# AEMLIC_V2_1.net
KiCad netlist of a schematic drawn in EAGLE
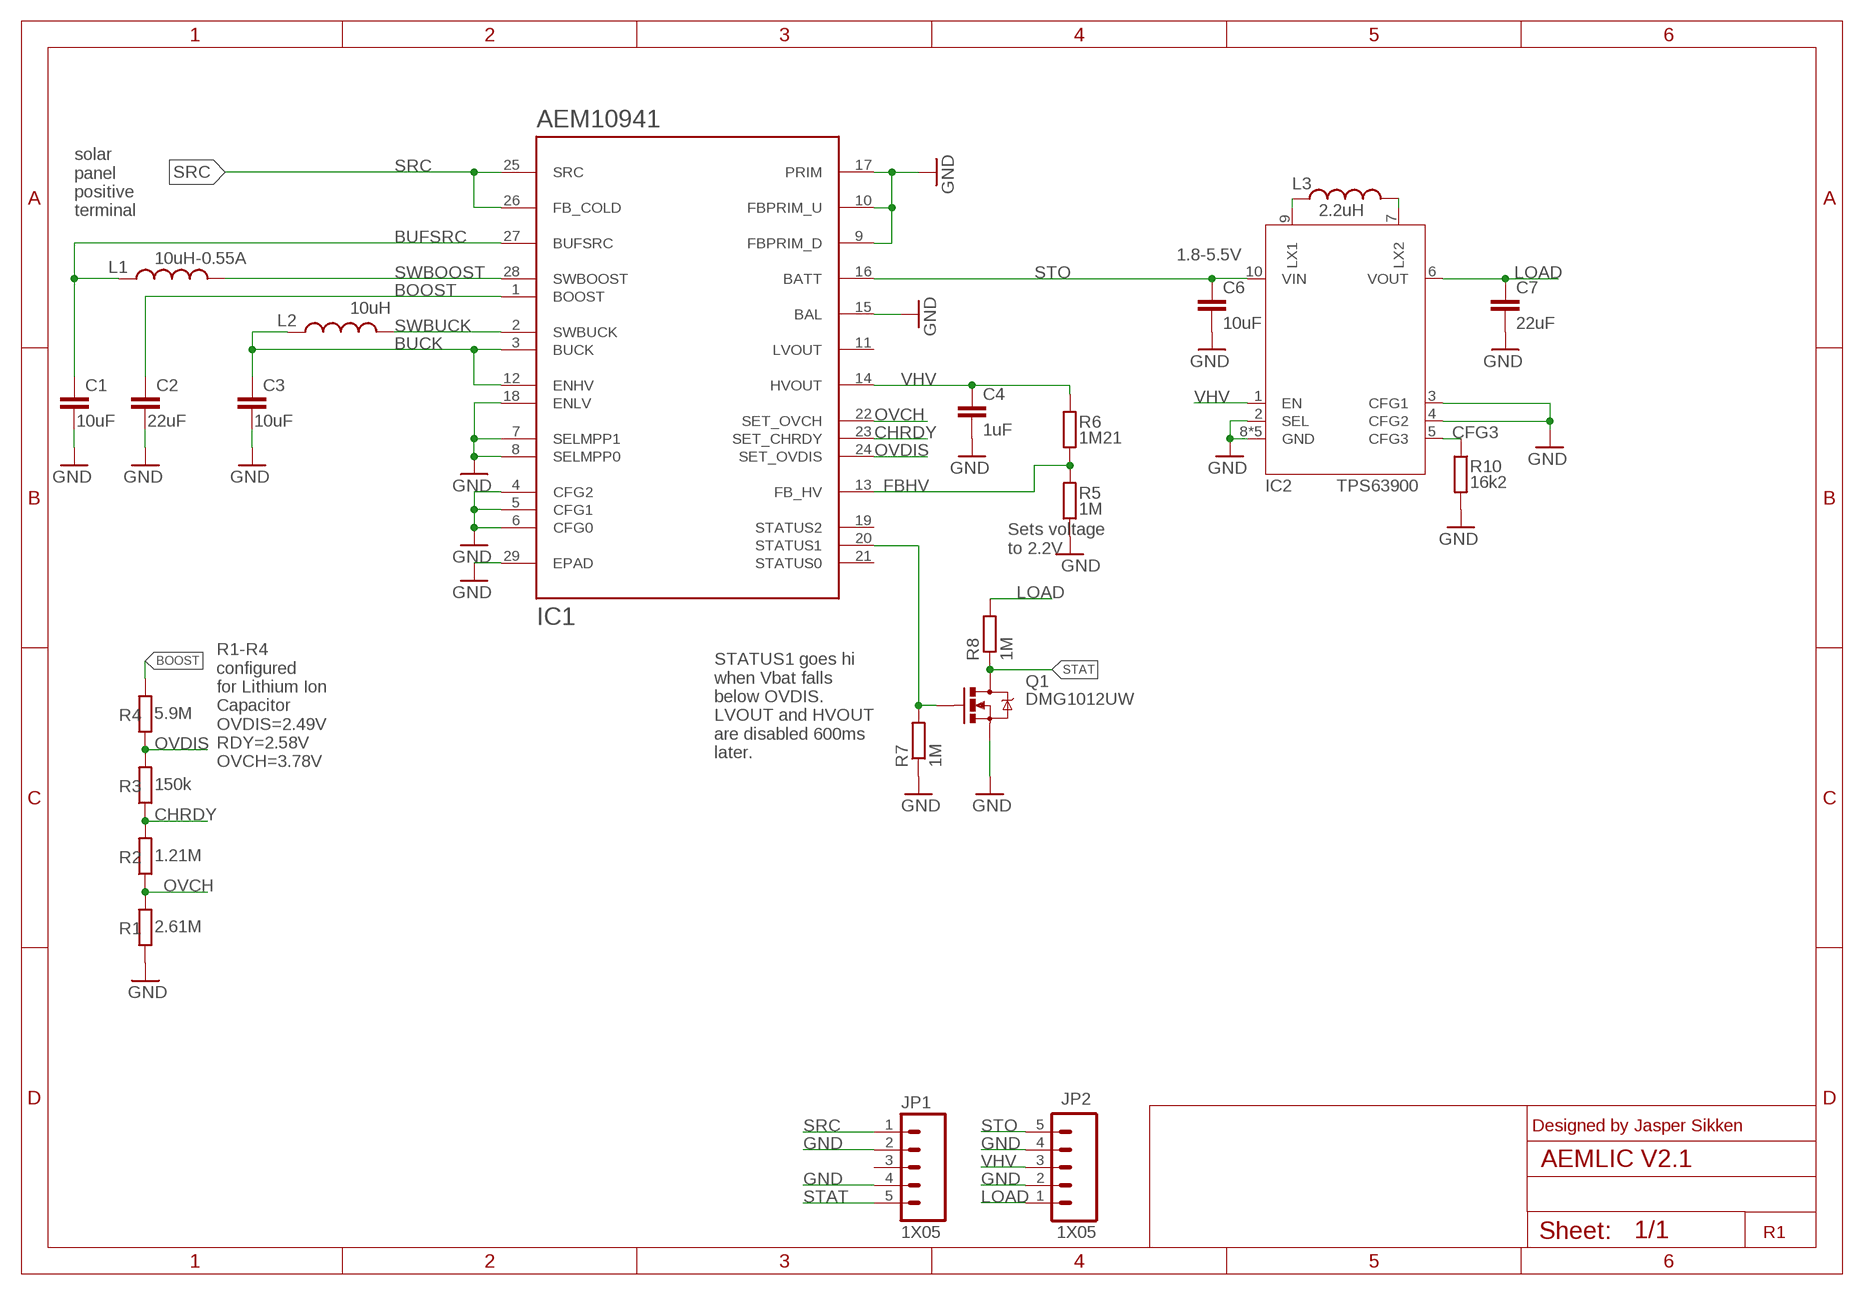
[diagram p0: schematic, sheet 1]

(export (version "E")
  (design (tool "Eeschema 10.0.6"))
  (components
    (comp (ref "C1")
      (value "10uF")
      (footprint "eagle-import:C0603")
      (fields
        (field (name "MF") "Taiyo Yuden")
        (field (name "MPN") "LMK107BBJ106MALT")
        (field (name "MF_1") "KEYSTONE")
        (field (name "MPN_1") "1049P")
      )
      (libsource (lib "eagle-import") (part "TSEM_C0603_10UF"))
    )
    (comp (ref "C2")
      (value "22uF")
      (footprint "eagle-import:C0603")
      (fields
        (field (name "MF") "Murata")
        (field (name "MPN") "GRM188R61A226ME15D")
        (field (name "MF_1") "TDK")
        (field (name "MPN_1") "CGA5L1X7S1A226M160AC")
      )
      (libsource (lib "eagle-import") (part "TSEM_C0603_22UF"))
    )
    (comp (ref "C3")
      (value "10uF")
      (footprint "eagle-import:C0603")
      (fields
        (field (name "MF") "Taiyo Yuden")
        (field (name "MPN") "LMK107BBJ106MALT")
        (field (name "MF_1") "KEYSTONE")
        (field (name "MPN_1") "1049P")
      )
      (libsource (lib "eagle-import") (part "TSEM_C0603_10UF"))
    )
    (comp (ref "C4")
      (value "1uF")
      (footprint "eagle-import:C0603")
      (fields (field (name "MF") "Taiyo Yuden") (field (name "MPN") "LMK107BBJ106MALT"))
      (libsource (lib "eagle-import") (part "TSEM_C0603_10UF"))
    )
    (comp (ref "C6")
      (value "10uF")
      (footprint "eagle-import:C0603")
      (fields (field (name "MF") "Taiyo Yuden") (field (name "MPN") "LMK107BBJ106MALT"))
      (libsource (lib "eagle-import") (part "C0603_10UF"))
    )
    (comp (ref "C7")
      (value "22uF")
      (footprint "eagle-import:C0603")
      (fields (field (name "MF") "Murata") (field (name "MPN") "GRM188R61A226ME15D"))
      (libsource (lib "eagle-import") (part "C0603_22UF"))
    )
    (comp (ref "IC1")
      (value "AEM10941")
      (footprint "eagle-import:QFN50P505X505X90-28")
      (fields (field (name "MF") "e-peas"))
      (libsource (lib "eagle-import") (part "AEM10941"))
    )
    (comp (ref "IC2")
      (value "TPS63900")
      (footprint "eagle-import:WSON10")
      (libsource (lib "eagle-import") (part "TPS63900"))
    )
    (comp (ref "JP1")
      (value "1X05")
      (footprint "eagle-import:1X05_2.54MM_ROUND_NOSILK")
      (libsource (lib "eagle-import") (part "1X05"))
    )
    (comp (ref "JP2")
      (value "1X05")
      (footprint "eagle-import:1X05_2.54MM_ROUND_NOSILK")
      (libsource (lib "eagle-import") (part "1X05"))
    )
    (comp (ref "L1")
      (value "10uH-0.55A")
      (footprint "eagle-import:LPS4012")
      (fields
        (field (name "MF") "Coilcraft")
        (field (name "MPN") "LPS4012-103MRB")
        (field (name "MF_1") "BOURNS")
        (field (name "MPN_1") "SRN2009T-100M")
      )
      (libsource (lib "eagle-import") (part "L3.9X3.9_10UH_0.55A"))
    )
    (comp (ref "L2")
      (value "10uH")
      (footprint "eagle-import:L0603")
      (fields
        (field (name "MF") "TDK")
        (field (name "MPN") "MLZ1608M100WT")
        (field (name "MF_1") "TAIYO YUDEN")
        (field (name "MPN_1") "CK2125100M-T")
      )
      (libsource (lib "eagle-import") (part "L0603_10UH"))
    )
    (comp (ref "L3")
      (value "2.2uH")
      (footprint "eagle-import:L_1008_[2520]")
      (fields (field (name "MF") "Murata") (field (name "MPN") "DFE252012F-2R2M=P2"))
      (libsource (lib "eagle-import") (part "L2"))
    )
    (comp (ref "Q1")
      (value "DMG1012UW")
      (footprint "eagle-import:SOT323")
      (fields (field (name "MF") "Diodes") (field (name "MPN") "DMG1012UW-7"))
      (libsource (lib "eagle-import") (part "MOSFET-N-CHANNEL_DMG1012UW"))
    )
    (comp (ref "R1")
      (value "2.61M")
      (footprint "eagle-import:R0402")
      (fields (field (name "MF") "Walsin") (field (name "MPN") "WR04X1004FTL"))
      (libsource (lib "eagle-import") (part "TSEM_R0402_1M"))
    )
    (comp (ref "R2")
      (value "1.21M")
      (footprint "eagle-import:R0402")
      (fields (field (name "MF") "Walsin") (field (name "MPN") "WR04X1004FTL"))
      (libsource (lib "eagle-import") (part "TSEM_R0402_1M"))
    )
    (comp (ref "R3")
      (value "150k")
      (footprint "eagle-import:R0402")
      (fields (field (name "MF") "Walsin") (field (name "MPN") "WR04X1004FTL"))
      (libsource (lib "eagle-import") (part "TSEM_R0402_1M"))
    )
    (comp (ref "R4")
      (value "5.9M")
      (footprint "eagle-import:R0402")
      (fields (field (name "MF") "Walsin") (field (name "MPN") "WR04X1004FTL"))
      (libsource (lib "eagle-import") (part "TSEM_R0402_1M"))
    )
    (comp (ref "R5")
      (value "1M")
      (footprint "eagle-import:R0402")
      (fields (field (name "MF") "Walsin") (field (name "MPN") "WR04X1004FTL"))
      (libsource (lib "eagle-import") (part "TSEM_R0402_1M"))
    )
    (comp (ref "R6")
      (value "1M21")
      (footprint "eagle-import:R0402")
      (fields (field (name "MF") "Walsin") (field (name "MPN") "WR04X1004FTL"))
      (libsource (lib "eagle-import") (part "TSEM_R0402_1M"))
    )
    (comp (ref "R7")
      (value "1M")
      (footprint "eagle-import:R0402")
      (fields (field (name "MF") "Walsin") (field (name "MPN") "WR04X1004FTL"))
      (libsource (lib "eagle-import") (part "TSEM_R0402_1M"))
    )
    (comp (ref "R8")
      (value "1M")
      (footprint "eagle-import:R0402")
      (fields (field (name "MF") "Walsin") (field (name "MPN") "WR04X1004FTL"))
      (libsource (lib "eagle-import") (part "TSEM_R0402_1M"))
    )
    (comp (ref "R10")
      (value "16k2")
      (footprint "eagle-import:R0402")
      (libsource (lib "eagle-import") (part "R0402_10K"))
    )
  )
  (nets
    (net (code "1") (name "/BUCK") (class "Default")
      (node (ref "C3") (pin "1") (pinfunction "1_1") (pintype "passive"))
      (node (ref "IC1") (pin "12") (pinfunction "ENHV_12") (pintype "bidirectional"))
      (node (ref "IC1") (pin "3") (pinfunction "BUCK_3") (pintype "bidirectional"))
      (node (ref "L2") (pin "1") (pinfunction "1_1") (pintype "passive"))
    )
    (net (code "2") (name "/BUFSRC") (class "Default")
      (node (ref "C1") (pin "1") (pinfunction "1_1") (pintype "passive"))
      (node (ref "IC1") (pin "27") (pinfunction "BUFSRC_27") (pintype "power_in"))
      (node (ref "L1") (pin "1") (pinfunction "1_1") (pintype "passive"))
    )
    (net (code "3") (name "/CFG3") (class "Default")
      (node (ref "IC2") (pin "5") (pinfunction "CFG3_5") (pintype "bidirectional"))
      (node (ref "R10") (pin "1") (pinfunction "1_1") (pintype "passive"))
    )
    (net (code "4") (name "/CHRDY") (class "Default")
      (node (ref "IC1") (pin "23") (pinfunction "SET_CHRDY_23") (pintype "bidirectional"))
      (node (ref "R2") (pin "2") (pinfunction "2_2") (pintype "passive"))
      (node (ref "R3") (pin "1") (pinfunction "1_1") (pintype "passive"))
    )
    (net (code "5") (name "/FBHV") (class "Default")
      (node (ref "IC1") (pin "13") (pinfunction "FB_HV_13") (pintype "bidirectional"))
      (node (ref "R5") (pin "2") (pinfunction "2_2") (pintype "passive"))
      (node (ref "R6") (pin "1") (pinfunction "1_1") (pintype "passive"))
    )
    (net (code "6") (name "/LOAD") (class "Default")
      (node (ref "C7") (pin "1") (pinfunction "1_1") (pintype "passive"))
      (node (ref "IC2") (pin "6") (pinfunction "VOUT_6") (pintype "bidirectional"))
      (node (ref "JP2") (pin "1") (pinfunction "1_1") (pintype "passive"))
      (node (ref "R8") (pin "2") (pinfunction "2_2") (pintype "passive"))
    )
    (net (code "7") (name "/OVCH") (class "Default")
      (node (ref "IC1") (pin "22") (pinfunction "SET_OVCH_22") (pintype "bidirectional"))
      (node (ref "R1") (pin "2") (pinfunction "2_2") (pintype "passive"))
      (node (ref "R2") (pin "1") (pinfunction "1_1") (pintype "passive"))
    )
    (net (code "8") (name "/OVDIS") (class "Default")
      (node (ref "IC1") (pin "24") (pinfunction "SET_OVDIS_24") (pintype "bidirectional"))
      (node (ref "R3") (pin "2") (pinfunction "2_2") (pintype "passive"))
      (node (ref "R4") (pin "1") (pinfunction "1_1") (pintype "passive"))
    )
    (net (code "9") (name "/STO") (class "Default")
      (node (ref "C6") (pin "1") (pinfunction "1_1") (pintype "passive"))
      (node (ref "IC1") (pin "16") (pinfunction "BATT_16") (pintype "bidirectional"))
      (node (ref "IC2") (pin "10") (pinfunction "VIN_10") (pintype "bidirectional"))
      (node (ref "JP2") (pin "5") (pinfunction "5_5") (pintype "passive"))
    )
    (net (code "10") (name "/SWBOOST") (class "Default")
      (node (ref "IC1") (pin "28") (pinfunction "SWBOOST_28") (pintype "power_in"))
      (node (ref "L1") (pin "2") (pinfunction "2_2") (pintype "passive"))
    )
    (net (code "11") (name "/SWBUCK") (class "Default")
      (node (ref "IC1") (pin "2") (pinfunction "SWBUCK_2") (pintype "bidirectional"))
      (node (ref "L2") (pin "2") (pinfunction "2_2") (pintype "passive"))
    )
    (net (code "12") (name "/VHV") (class "Default")
      (node (ref "C4") (pin "1") (pinfunction "1_1") (pintype "passive"))
      (node (ref "IC1") (pin "14") (pinfunction "HVOUT_14") (pintype "bidirectional"))
      (node (ref "IC2") (pin "1") (pinfunction "EN_1") (pintype "bidirectional"))
      (node (ref "JP2") (pin "3") (pinfunction "3_3") (pintype "passive"))
      (node (ref "R6") (pin "2") (pinfunction "2_2") (pintype "passive"))
    )
    (net (code "13") (name "BOOST") (class "Default")
      (node (ref "C2") (pin "1") (pinfunction "1_1") (pintype "passive"))
      (node (ref "IC1") (pin "1") (pinfunction "BOOST_1") (pintype "bidirectional"))
      (node (ref "R4") (pin "2") (pinfunction "2_2") (pintype "passive"))
    )
    (net (code "14") (name "GND") (class "Default")
      (node (ref "C1") (pin "2") (pinfunction "2_2") (pintype "passive"))
      (node (ref "C2") (pin "2") (pinfunction "2_2") (pintype "passive"))
      (node (ref "C3") (pin "2") (pinfunction "2_2") (pintype "passive"))
      (node (ref "C4") (pin "2") (pinfunction "2_2") (pintype "passive"))
      (node (ref "C6") (pin "2") (pinfunction "2_2") (pintype "passive"))
      (node (ref "C7") (pin "2") (pinfunction "2_2") (pintype "passive"))
      (node (ref "IC1") (pin "10") (pinfunction "FBPRIM_U_10") (pintype "bidirectional"))
      (node (ref "IC1") (pin "15") (pinfunction "BAL_15") (pintype "bidirectional"))
      (node (ref "IC1") (pin "17") (pinfunction "PRIM_17") (pintype "bidirectional"))
      (node (ref "IC1") (pin "18") (pinfunction "ENLV_18") (pintype "bidirectional"))
      (node (ref "IC1") (pin "29") (pinfunction "EPAD_29") (pintype "power_in"))
      (node (ref "IC1") (pin "4") (pinfunction "CFG2_4") (pintype "bidirectional"))
      (node (ref "IC1") (pin "5") (pinfunction "CFG1_5") (pintype "bidirectional"))
      (node (ref "IC1") (pin "6") (pinfunction "CFG0_6") (pintype "bidirectional"))
      (node (ref "IC1") (pin "7") (pinfunction "SELMPP1_7") (pintype "bidirectional"))
      (node (ref "IC1") (pin "8") (pinfunction "SELMPP0_8") (pintype "bidirectional"))
      (node (ref "IC1") (pin "9") (pinfunction "FBPRIM_D_9") (pintype "bidirectional"))
      (node (ref "IC2") (pin "2") (pinfunction "SEL_2") (pintype "bidirectional"))
      (node (ref "IC2") (pin "29") (pinfunction "GND_29") (pintype "bidirectional"))
      (node (ref "IC2") (pin "3") (pinfunction "CFG1_3") (pintype "bidirectional"))
      (node (ref "IC2") (pin "4") (pinfunction "CFG2_4") (pintype "bidirectional"))
      (node (ref "IC2") (pin "8") (pinfunction "GND_8") (pintype "bidirectional"))
      (node (ref "IC2") (pin "P$2") (pinfunction "GND_P$2") (pintype "bidirectional"))
      (node (ref "IC2") (pin "P$4") (pinfunction "GND_P$4") (pintype "bidirectional"))
      (node (ref "IC2") (pin "P$5") (pinfunction "GND_P$5") (pintype "bidirectional"))
      (node (ref "JP1") (pin "2") (pinfunction "2_2") (pintype "passive"))
      (node (ref "JP1") (pin "4") (pinfunction "4_4") (pintype "passive"))
      (node (ref "JP2") (pin "2") (pinfunction "2_2") (pintype "passive"))
      (node (ref "JP2") (pin "4") (pinfunction "4_4") (pintype "passive"))
      (node (ref "Q1") (pin "2") (pinfunction "S_2") (pintype "passive"))
      (node (ref "R1") (pin "1") (pinfunction "1_1") (pintype "passive"))
      (node (ref "R10") (pin "2") (pinfunction "2_2") (pintype "passive"))
      (node (ref "R5") (pin "1") (pinfunction "1_1") (pintype "passive"))
      (node (ref "R7") (pin "1") (pinfunction "1_1") (pintype "passive"))
    )
    (net (code "15") (name "Net-(IC1-STATUS1)") (class "Default")
      (node (ref "IC1") (pin "20") (pinfunction "STATUS1_20") (pintype "bidirectional"))
      (node (ref "Q1") (pin "1") (pinfunction "G_1") (pintype "passive"))
      (node (ref "R7") (pin "2") (pinfunction "2_2") (pintype "passive"))
    )
    (net (code "16") (name "Net-(IC2-LX1)") (class "Default")
      (node (ref "IC2") (pin "9") (pinfunction "LX1_9") (pintype "bidirectional"))
      (node (ref "L3") (pin "1") (pinfunction "1_1") (pintype "passive"))
    )
    (net (code "17") (name "Net-(IC2-LX2)") (class "Default")
      (node (ref "IC2") (pin "7") (pinfunction "LX2_7") (pintype "bidirectional"))
      (node (ref "L3") (pin "2") (pinfunction "2_2") (pintype "passive"))
    )
    (net (code "18") (name "SRC") (class "Default")
      (node (ref "IC1") (pin "25") (pinfunction "SRC_25") (pintype "power_in"))
      (node (ref "IC1") (pin "26") (pinfunction "FB_COLD_26") (pintype "input"))
      (node (ref "JP1") (pin "1") (pinfunction "1_1") (pintype "passive"))
    )
    (net (code "19") (name "STAT") (class "Default")
      (node (ref "JP1") (pin "5") (pinfunction "5_5") (pintype "passive"))
      (node (ref "Q1") (pin "3") (pinfunction "D_3") (pintype "passive"))
      (node (ref "R8") (pin "1") (pinfunction "1_1") (pintype "passive"))
    )
    (net (code "20") (name "unconnected-(IC1-LVOUT-Pad11)") (class "Default")
      (node (ref "IC1") (pin "11") (pinfunction "LVOUT_11") (pintype "bidirectional"))
    )
    (net (code "21") (name "unconnected-(IC1-STATUS0-Pad21)") (class "Default")
      (node (ref "IC1") (pin "21") (pinfunction "STATUS0_21") (pintype "bidirectional"))
    )
    (net (code "22") (name "unconnected-(IC1-STATUS2-Pad19)") (class "Default")
      (node (ref "IC1") (pin "19") (pinfunction "STATUS2_19") (pintype "bidirectional"))
    )
    (net (code "23") (name "unconnected-(JP1-Pad3)") (class "Default")
      (node (ref "JP1") (pin "3") (pinfunction "3_3") (pintype "passive"))
    )
  )
)
